# Fan_driver.net
KiCad netlist of a schematic drawn in Altium Designer
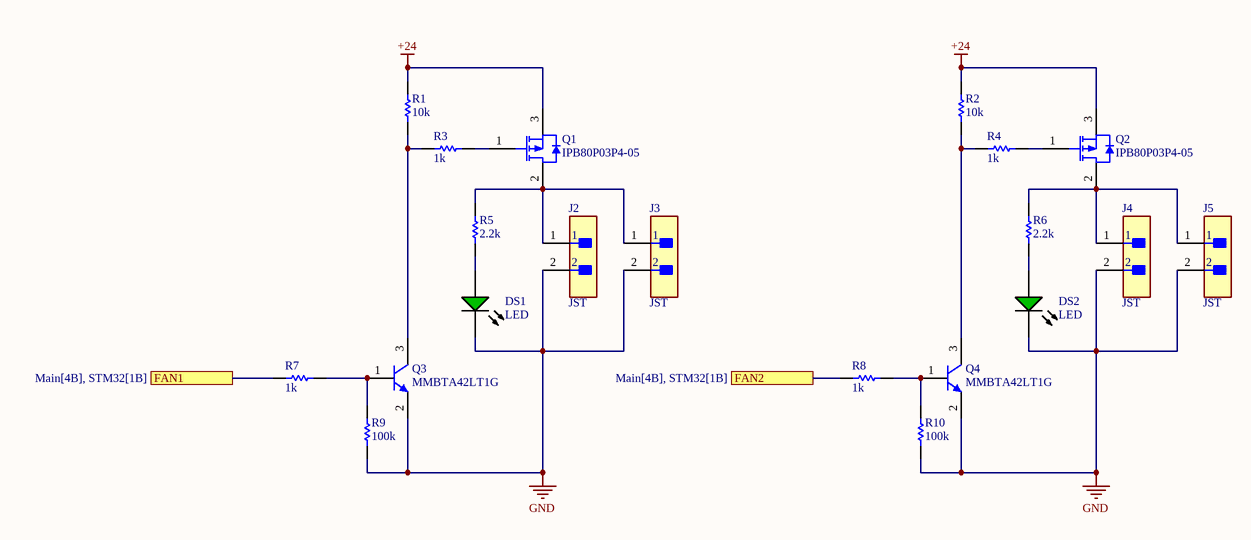
[diagram p0: Fan_driver.SchDoc]

(export (version "E")
  (design (tool "Eeschema 10.0.6"))
  (components
    (comp (ref "DS1")
      (value "LED")
      (footprint "AVAG-HSMX-C170_V")
      (description "Chip LED, Green, 2.2 V, -40 to 85 degC, 2-Pin SMD, Pb-Free, Tape and Reel")
      (fields (field (name "MANUFACTURER") "Avago"))
      (libsource (lib "Altium Content Vault") (part "LED_GREEN_A1K2-2"))
    )
    (comp (ref "DS2")
      (value "LED")
      (footprint "AVAG-HSMX-C170_V")
      (description "Chip LED, Green, 2.2 V, -40 to 85 degC, 2-Pin SMD, Pb-Free, Tape and Reel")
      (fields (field (name "MANUFACTURER") "Avago"))
      (libsource (lib "Altium Content Vault") (part "LED_GREEN_A1K2-2"))
    )
    (comp (ref "J2")
      (value "JST")
      (footprint "FP-B2B-EH-A_LF_SN-MFG")
      (description "CONN HEADER VERT 2POS 2.5MM")
      (libsource (lib "Altium Content Vault") (part "3bc925449376181038e59eaffc5286c"))
    )
    (comp (ref "J3")
      (value "JST")
      (footprint "FP-B2B-EH-A_LF_SN-MFG")
      (description "CONN HEADER VERT 2POS 2.5MM")
      (libsource (lib "Altium Content Vault") (part "3bc925449376181038e59eaffc5286c"))
    )
    (comp (ref "J4")
      (value "JST")
      (footprint "FP-B2B-EH-A_LF_SN-MFG")
      (description "CONN HEADER VERT 2POS 2.5MM")
      (libsource (lib "Altium Content Vault") (part "3bc925449376181038e59eaffc5286c"))
    )
    (comp (ref "J5")
      (value "JST")
      (footprint "FP-B2B-EH-A_LF_SN-MFG")
      (description "CONN HEADER VERT 2POS 2.5MM")
      (libsource (lib "Altium Content Vault") (part "3bc925449376181038e59eaffc5286c"))
    )
    (comp (ref "Q1")
      (value "IPB80P03P4-05")
      (footprint "INF-PG-TO263-3-2_N")
      (description "OptiMOS-P2 Power-Transistor, -30 V VDS, -80 A ID, PG-TO263-3-2, Reel, Green")
      (fields (field (name "MANUFACTURER") "Infineon"))
      (libsource (lib "Altium Content Vault") (part "INF-MOSFET-P-3"))
    )
    (comp (ref "Q2")
      (value "IPB80P03P4-05")
      (footprint "INF-PG-TO263-3-2_N")
      (description "OptiMOS-P2 Power-Transistor, -30 V VDS, -80 A ID, PG-TO263-3-2, Reel, Green")
      (fields (field (name "MANUFACTURER") "Infineon"))
      (libsource (lib "Altium Content Vault") (part "INF-MOSFET-P-3"))
    )
    (comp (ref "Q3")
      (value "MMBTA42LT1G")
      (footprint "ONSC-SOT-23-3-318-08_V")
      (description "High Voltage Transistor, NPN Silicon, 3-Pin SOT-23, Pb-Free, Tape and Reel")
      (fields (field (name "MANUFACTURER") "On Semiconductor"))
      (libsource (lib "Altium Content Vault") (part "ONSC-NPN-B1E2C3-3"))
    )
    (comp (ref "Q4")
      (value "MMBTA42LT1G")
      (footprint "ONSC-SOT-23-3-318-08_V")
      (description "High Voltage Transistor, NPN Silicon, 3-Pin SOT-23, Pb-Free, Tape and Reel")
      (fields (field (name "MANUFACTURER") "On Semiconductor"))
      (libsource (lib "Altium Content Vault") (part "ONSC-NPN-B1E2C3-3"))
    )
    (comp (ref "R1")
      (value "10k")
      (footprint "RESC2013X50X30LL20T20")
      (fields (field (name "MANUFACTURER") "Vishay Dale") (field (name "PART NUMBER") "CRCW08050000Z0EA"))
      (libsource (lib "Altium Content Vault") (part "RES"))
    )
    (comp (ref "R2")
      (value "10k")
      (footprint "RESC2013X50X30LL20T20")
      (fields (field (name "MANUFACTURER") "Vishay Dale") (field (name "PART NUMBER") "CRCW08050000Z0EA"))
      (libsource (lib "Altium Content Vault") (part "RES"))
    )
    (comp (ref "R3")
      (value "1k")
      (footprint "RESC2013X50X30LL20T20")
      (fields (field (name "MANUFACTURER") "Vishay Dale") (field (name "PART NUMBER") "CRCW08050000Z0EA"))
      (libsource (lib "Altium Content Vault") (part "RES"))
    )
    (comp (ref "R4")
      (value "1k")
      (footprint "RESC2013X50X30LL20T20")
      (fields (field (name "MANUFACTURER") "Vishay Dale") (field (name "PART NUMBER") "CRCW08050000Z0EA"))
      (libsource (lib "Altium Content Vault") (part "RES"))
    )
    (comp (ref "R5")
      (value "2.2k")
      (footprint "RESC2013X50X30LL20T20")
      (fields (field (name "MANUFACTURER") "Vishay Dale") (field (name "PART NUMBER") "CRCW08050000Z0EA"))
      (libsource (lib "Altium Content Vault") (part "RES"))
    )
    (comp (ref "R6")
      (value "2.2k")
      (footprint "RESC2013X50X30LL20T20")
      (fields (field (name "MANUFACTURER") "Vishay Dale") (field (name "PART NUMBER") "CRCW08050000Z0EA"))
      (libsource (lib "Altium Content Vault") (part "RES"))
    )
    (comp (ref "R7")
      (value "1k")
      (footprint "RESC2013X50X30LL20T20")
      (fields (field (name "MANUFACTURER") "Vishay Dale") (field (name "PART NUMBER") "CRCW08050000Z0EA"))
      (libsource (lib "Altium Content Vault") (part "RES"))
    )
    (comp (ref "R8")
      (value "1k")
      (footprint "RESC2013X50X30LL20T20")
      (fields (field (name "MANUFACTURER") "Vishay Dale") (field (name "PART NUMBER") "CRCW08050000Z0EA"))
      (libsource (lib "Altium Content Vault") (part "RES"))
    )
    (comp (ref "R9")
      (value "100k")
      (footprint "RESC2013X50X30LL20T20")
      (fields (field (name "MANUFACTURER") "Vishay Dale") (field (name "PART NUMBER") "CRCW08050000Z0EA"))
      (libsource (lib "Altium Content Vault") (part "RES"))
    )
    (comp (ref "R10")
      (value "100k")
      (footprint "RESC2013X50X30LL20T20")
      (fields (field (name "MANUFACTURER") "Vishay Dale") (field (name "PART NUMBER") "CRCW08050000Z0EA"))
      (libsource (lib "Altium Content Vault") (part "RES"))
    )
  )
  (nets
    (net (code "1") (name "+24") (class "Default")
      (node (ref "Q1") (pin "3") (pinfunction "SOURCE_3") (pintype "passive"))
      (node (ref "Q2") (pin "3") (pinfunction "SOURCE_3") (pintype "passive"))
      (node (ref "R1") (pin "2") (pinfunction "2_2") (pintype "passive"))
      (node (ref "R2") (pin "2") (pinfunction "2_2") (pintype "passive"))
    )
    (net (code "2") (name "/FAN1") (class "Default")
      (node (ref "R7") (pin "1") (pinfunction "1_1") (pintype "passive"))
    )
    (net (code "3") (name "/FAN2") (class "Default")
      (node (ref "R8") (pin "1") (pinfunction "1_1") (pintype "passive"))
    )
    (net (code "4") (name "GND") (class "Default")
      (node (ref "DS1") (pin "2") (pinfunction "K_2") (pintype "passive"))
      (node (ref "DS2") (pin "2") (pinfunction "K_2") (pintype "passive"))
      (node (ref "J2") (pin "2") (pinfunction "2_2") (pintype "passive"))
      (node (ref "J3") (pin "2") (pinfunction "2_2") (pintype "passive"))
      (node (ref "J4") (pin "2") (pinfunction "2_2") (pintype "passive"))
      (node (ref "J5") (pin "2") (pinfunction "2_2") (pintype "passive"))
      (node (ref "Q3") (pin "2") (pinfunction "E_2") (pintype "passive"))
      (node (ref "Q4") (pin "2") (pinfunction "E_2") (pintype "passive"))
      (node (ref "R10") (pin "1") (pinfunction "1_1") (pintype "passive"))
      (node (ref "R9") (pin "1") (pinfunction "1_1") (pintype "passive"))
    )
    (net (code "5") (name "Net-(DS1-A)") (class "Default")
      (node (ref "DS1") (pin "1") (pinfunction "A_1") (pintype "passive"))
      (node (ref "R5") (pin "1") (pinfunction "1_1") (pintype "passive"))
    )
    (net (code "6") (name "Net-(DS2-A)") (class "Default")
      (node (ref "DS2") (pin "1") (pinfunction "A_1") (pintype "passive"))
      (node (ref "R6") (pin "1") (pinfunction "1_1") (pintype "passive"))
    )
    (net (code "7") (name "Net-(Q1-DRAIN)") (class "Default")
      (node (ref "J2") (pin "1") (pinfunction "1_1") (pintype "passive"))
      (node (ref "J3") (pin "1") (pinfunction "1_1") (pintype "passive"))
      (node (ref "Q1") (pin "2") (pinfunction "DRAIN_2") (pintype "passive"))
      (node (ref "R5") (pin "2") (pinfunction "2_2") (pintype "passive"))
    )
    (net (code "8") (name "Net-(Q1-GATE)") (class "Default")
      (node (ref "Q1") (pin "1") (pinfunction "GATE_1") (pintype "passive"))
      (node (ref "R3") (pin "2") (pinfunction "2_2") (pintype "passive"))
    )
    (net (code "9") (name "Net-(Q2-DRAIN)") (class "Default")
      (node (ref "J4") (pin "1") (pinfunction "1_1") (pintype "passive"))
      (node (ref "J5") (pin "1") (pinfunction "1_1") (pintype "passive"))
      (node (ref "Q2") (pin "2") (pinfunction "DRAIN_2") (pintype "passive"))
      (node (ref "R6") (pin "2") (pinfunction "2_2") (pintype "passive"))
    )
    (net (code "10") (name "Net-(Q2-GATE)") (class "Default")
      (node (ref "Q2") (pin "1") (pinfunction "GATE_1") (pintype "passive"))
      (node (ref "R4") (pin "2") (pinfunction "2_2") (pintype "passive"))
    )
    (net (code "11") (name "Net-(Q3-B)") (class "Default")
      (node (ref "Q3") (pin "1") (pinfunction "B_1") (pintype "passive"))
      (node (ref "R7") (pin "2") (pinfunction "2_2") (pintype "passive"))
      (node (ref "R9") (pin "2") (pinfunction "2_2") (pintype "passive"))
    )
    (net (code "12") (name "Net-(Q3-C)") (class "Default")
      (node (ref "Q3") (pin "3") (pinfunction "C_3") (pintype "passive"))
      (node (ref "R1") (pin "1") (pinfunction "1_1") (pintype "passive"))
      (node (ref "R3") (pin "1") (pinfunction "1_1") (pintype "passive"))
    )
    (net (code "13") (name "Net-(Q4-B)") (class "Default")
      (node (ref "Q4") (pin "1") (pinfunction "B_1") (pintype "passive"))
      (node (ref "R10") (pin "2") (pinfunction "2_2") (pintype "passive"))
      (node (ref "R8") (pin "2") (pinfunction "2_2") (pintype "passive"))
    )
    (net (code "14") (name "Net-(Q4-C)") (class "Default")
      (node (ref "Q4") (pin "3") (pinfunction "C_3") (pintype "passive"))
      (node (ref "R2") (pin "1") (pinfunction "1_1") (pintype "passive"))
      (node (ref "R4") (pin "1") (pinfunction "1_1") (pintype "passive"))
    )
  )
)
